# Connector.net
KiCad netlist of a schematic drawn in Altium Designer
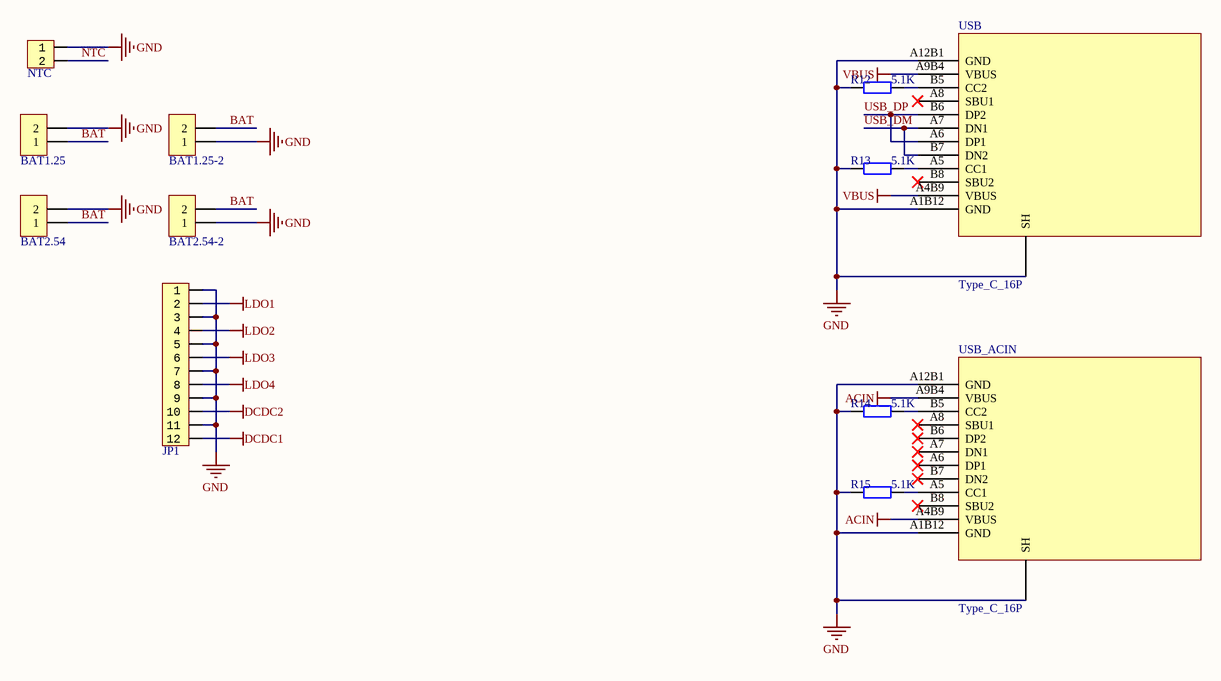
[diagram p0: Connector.SchDoc]

(export (version "E")
  (design (tool "Eeschema 10.0.6"))
  (components
    (comp (ref "BAT1.25")
      (value "HDR-1X2")
      (footprint "MX 1.25-WS-2P")
      (description "2P接插件")
      (fields (field (name "版权归属") "源创客"))
      (libsource (lib "4.2   - 接插件-脚距1.25") (part "Header 2"))
    )
    (comp (ref "BAT1.25-2")
      (value "HDR-1X2")
      (footprint "MX 1.25-WS-2P")
      (description "2P接插件")
      (fields (field (name "版权归属") "源创客"))
      (libsource (lib "4.2   - 接插件-脚距1.25") (part "Header 2"))
    )
    (comp (ref "BAT2.54")
      (value "HDR-1X2")
      (footprint "XH2.54-WS-2P")
      (description "2P接插件")
      (fields (field (name "版权归属") "源创客"))
      (libsource (lib "4.5   - 接插件-脚距2.54") (part "Header 2"))
    )
    (comp (ref "BAT2.54-2")
      (value "HDR-1X2")
      (footprint "XH2.54-WS-2P")
      (description "2P接插件")
      (fields (field (name "版权归属") "源创客"))
      (libsource (lib "4.5   - 接插件-脚距2.54") (part "Header 2"))
    )
    (comp (ref "JP1")
      (value "HDR1x12_2.54T")
      (footprint "PCB_ConnectorHDR:HDR1X12_2.54_90")
      (description "Header")
      (libsource (lib "SCH_ConnectorHDR") (part "HDR1x12_2.54T"))
    )
    (comp (ref "NTC")
      (value "HDR1x2_1.27T")
      (footprint "PCB_ConnectorHDR:HDR1X2_1.27_180")
      (description "Header")
      (libsource (lib "SCH_ConnectorHDR") (part "HDR1x2_1.27T"))
    )
    (comp (ref "R12")
      (value "5.1K")
      (footprint "R 0603_L")
      (description "贴片电阻")
      (fields (field (name "版权归属") "源创客"))
      (libsource (lib "3.1   - 电阻-电容-电感") (part "R"))
    )
    (comp (ref "R13")
      (value "5.1K")
      (footprint "R 0603_L")
      (description "贴片电阻")
      (fields (field (name "版权归属") "源创客"))
      (libsource (lib "3.1   - 电阻-电容-电感") (part "R"))
    )
    (comp (ref "R14")
      (value "5.1K")
      (footprint "R 0603_L")
      (description "贴片电阻")
      (fields (field (name "版权归属") "源创客"))
      (libsource (lib "3.1   - 电阻-电容-电感") (part "R"))
    )
    (comp (ref "R15")
      (value "5.1K")
      (footprint "R 0603_L")
      (description "贴片电阻")
      (fields (field (name "版权归属") "源创客"))
      (libsource (lib "3.1   - 电阻-电容-电感") (part "R"))
    )
    (comp (ref "USB")
      (value "Type_C_16P")
      (footprint "Type_C_16P")
      (libsource (lib "LuLib") (part "Type_C_16P"))
    )
    (comp (ref "USB_ACIN")
      (value "Type_C_16P")
      (footprint "Type_C_16P")
      (libsource (lib "LuLib") (part "Type_C_16P"))
    )
  )
  (nets
    (net (code "1") (name "/BAT") (class "Default")
      (node (ref "BAT1.25") (pin "1") (pinfunction "1_1") (pintype "passive"))
      (node (ref "BAT1.25-2") (pin "2") (pinfunction "2_2") (pintype "passive"))
      (node (ref "BAT2.54") (pin "1") (pinfunction "1_1") (pintype "passive"))
      (node (ref "BAT2.54-2") (pin "2") (pinfunction "2_2") (pintype "passive"))
    )
    (net (code "2") (name "/NTC") (class "Default")
      (node (ref "NTC") (pin "2") (pinfunction "2_2") (pintype "passive"))
    )
    (net (code "3") (name "/USB_DM") (class "Default")
      (node (ref "USB") (pin "A7") (pinfunction "DN1_A7") (pintype "passive"))
      (node (ref "USB") (pin "B7") (pinfunction "DN2_B7") (pintype "passive"))
    )
    (net (code "4") (name "/USB_DP") (class "Default")
      (node (ref "USB") (pin "A6") (pinfunction "DP1_A6") (pintype "passive"))
      (node (ref "USB") (pin "B6") (pinfunction "DP2_B6") (pintype "passive"))
    )
    (net (code "5") (name "ACIN") (class "Default")
      (node (ref "USB_ACIN") (pin "A4B9") (pinfunction "VBUS_A4B9") (pintype "passive"))
      (node (ref "USB_ACIN") (pin "A9B4") (pinfunction "VBUS_A9B4") (pintype "passive"))
    )
    (net (code "6") (name "DCDC1") (class "Default")
      (node (ref "JP1") (pin "12") (pinfunction "12_12") (pintype "passive"))
    )
    (net (code "7") (name "DCDC2") (class "Default")
      (node (ref "JP1") (pin "10") (pinfunction "10_10") (pintype "passive"))
    )
    (net (code "8") (name "GND") (class "Default")
      (node (ref "BAT1.25") (pin "2") (pinfunction "2_2") (pintype "passive"))
      (node (ref "BAT1.25-2") (pin "1") (pinfunction "1_1") (pintype "passive"))
      (node (ref "BAT2.54") (pin "2") (pinfunction "2_2") (pintype "passive"))
      (node (ref "BAT2.54-2") (pin "1") (pinfunction "1_1") (pintype "passive"))
      (node (ref "JP1") (pin "1") (pinfunction "1_1") (pintype "passive"))
      (node (ref "JP1") (pin "11") (pinfunction "11_11") (pintype "passive"))
      (node (ref "JP1") (pin "3") (pinfunction "3_3") (pintype "passive"))
      (node (ref "JP1") (pin "5") (pinfunction "5_5") (pintype "passive"))
      (node (ref "JP1") (pin "7") (pinfunction "7_7") (pintype "passive"))
      (node (ref "JP1") (pin "9") (pinfunction "9_9") (pintype "passive"))
      (node (ref "NTC") (pin "1") (pinfunction "1_1") (pintype "passive"))
      (node (ref "R12") (pin "1") (pinfunction "1_1") (pintype "passive"))
      (node (ref "R13") (pin "1") (pinfunction "1_1") (pintype "passive"))
      (node (ref "R14") (pin "1") (pinfunction "1_1") (pintype "passive"))
      (node (ref "R15") (pin "1") (pinfunction "1_1") (pintype "passive"))
      (node (ref "USB") (pin "0") (pinfunction "SH_0") (pintype "passive"))
      (node (ref "USB") (pin "A12B1") (pinfunction "GND_A12B1") (pintype "passive"))
      (node (ref "USB") (pin "A1B12") (pinfunction "GND_A1B12") (pintype "passive"))
      (node (ref "USB_ACIN") (pin "0") (pinfunction "SH_0") (pintype "passive"))
      (node (ref "USB_ACIN") (pin "A12B1") (pinfunction "GND_A12B1") (pintype "passive"))
      (node (ref "USB_ACIN") (pin "A1B12") (pinfunction "GND_A1B12") (pintype "passive"))
    )
    (net (code "9") (name "LDO1") (class "Default")
      (node (ref "JP1") (pin "2") (pinfunction "2_2") (pintype "passive"))
    )
    (net (code "10") (name "LDO2") (class "Default")
      (node (ref "JP1") (pin "4") (pinfunction "4_4") (pintype "passive"))
    )
    (net (code "11") (name "LDO3") (class "Default")
      (node (ref "JP1") (pin "6") (pinfunction "6_6") (pintype "passive"))
    )
    (net (code "12") (name "LDO4") (class "Default")
      (node (ref "JP1") (pin "8") (pinfunction "8_8") (pintype "passive"))
    )
    (net (code "13") (name "Net-(USB-CC1)") (class "Default")
      (node (ref "R13") (pin "2") (pinfunction "2_2") (pintype "passive"))
      (node (ref "USB") (pin "A5") (pinfunction "CC1_A5") (pintype "passive"))
    )
    (net (code "14") (name "Net-(USB-CC2)") (class "Default")
      (node (ref "R12") (pin "2") (pinfunction "2_2") (pintype "passive"))
      (node (ref "USB") (pin "B5") (pinfunction "CC2_B5") (pintype "passive"))
    )
    (net (code "15") (name "Net-(USB_ACIN-CC1)") (class "Default")
      (node (ref "R15") (pin "2") (pinfunction "2_2") (pintype "passive"))
      (node (ref "USB_ACIN") (pin "A5") (pinfunction "CC1_A5") (pintype "passive"))
    )
    (net (code "16") (name "Net-(USB_ACIN-CC2)") (class "Default")
      (node (ref "R14") (pin "2") (pinfunction "2_2") (pintype "passive"))
      (node (ref "USB_ACIN") (pin "B5") (pinfunction "CC2_B5") (pintype "passive"))
    )
    (net (code "17") (name "VBUS") (class "Default")
      (node (ref "USB") (pin "A4B9") (pinfunction "VBUS_A4B9") (pintype "passive"))
      (node (ref "USB") (pin "A9B4") (pinfunction "VBUS_A9B4") (pintype "passive"))
    )
    (net (code "18") (name "unconnected-(USB-SBU1-PadA8)") (class "Default")
      (node (ref "USB") (pin "A8") (pinfunction "SBU1_A8") (pintype "passive+no_connect"))
    )
    (net (code "19") (name "unconnected-(USB-SBU2-PadB8)") (class "Default")
      (node (ref "USB") (pin "B8") (pinfunction "SBU2_B8") (pintype "passive+no_connect"))
    )
    (net (code "20") (name "unconnected-(USB_ACIN-DN1-PadA7)") (class "Default")
      (node (ref "USB_ACIN") (pin "A7") (pinfunction "DN1_A7") (pintype "passive+no_connect"))
    )
    (net (code "21") (name "unconnected-(USB_ACIN-DN2-PadB7)") (class "Default")
      (node (ref "USB_ACIN") (pin "B7") (pinfunction "DN2_B7") (pintype "passive+no_connect"))
    )
    (net (code "22") (name "unconnected-(USB_ACIN-DP1-PadA6)") (class "Default")
      (node (ref "USB_ACIN") (pin "A6") (pinfunction "DP1_A6") (pintype "passive+no_connect"))
    )
    (net (code "23") (name "unconnected-(USB_ACIN-DP2-PadB6)") (class "Default")
      (node (ref "USB_ACIN") (pin "B6") (pinfunction "DP2_B6") (pintype "passive+no_connect"))
    )
    (net (code "24") (name "unconnected-(USB_ACIN-SBU1-PadA8)") (class "Default")
      (node (ref "USB_ACIN") (pin "A8") (pinfunction "SBU1_A8") (pintype "passive+no_connect"))
    )
    (net (code "25") (name "unconnected-(USB_ACIN-SBU2-PadB8)") (class "Default")
      (node (ref "USB_ACIN") (pin "B8") (pinfunction "SBU2_B8") (pintype "passive+no_connect"))
    )
  )
)
